# x-OSC_Gloves_v6.net
KiCad netlist of a schematic drawn in EAGLE
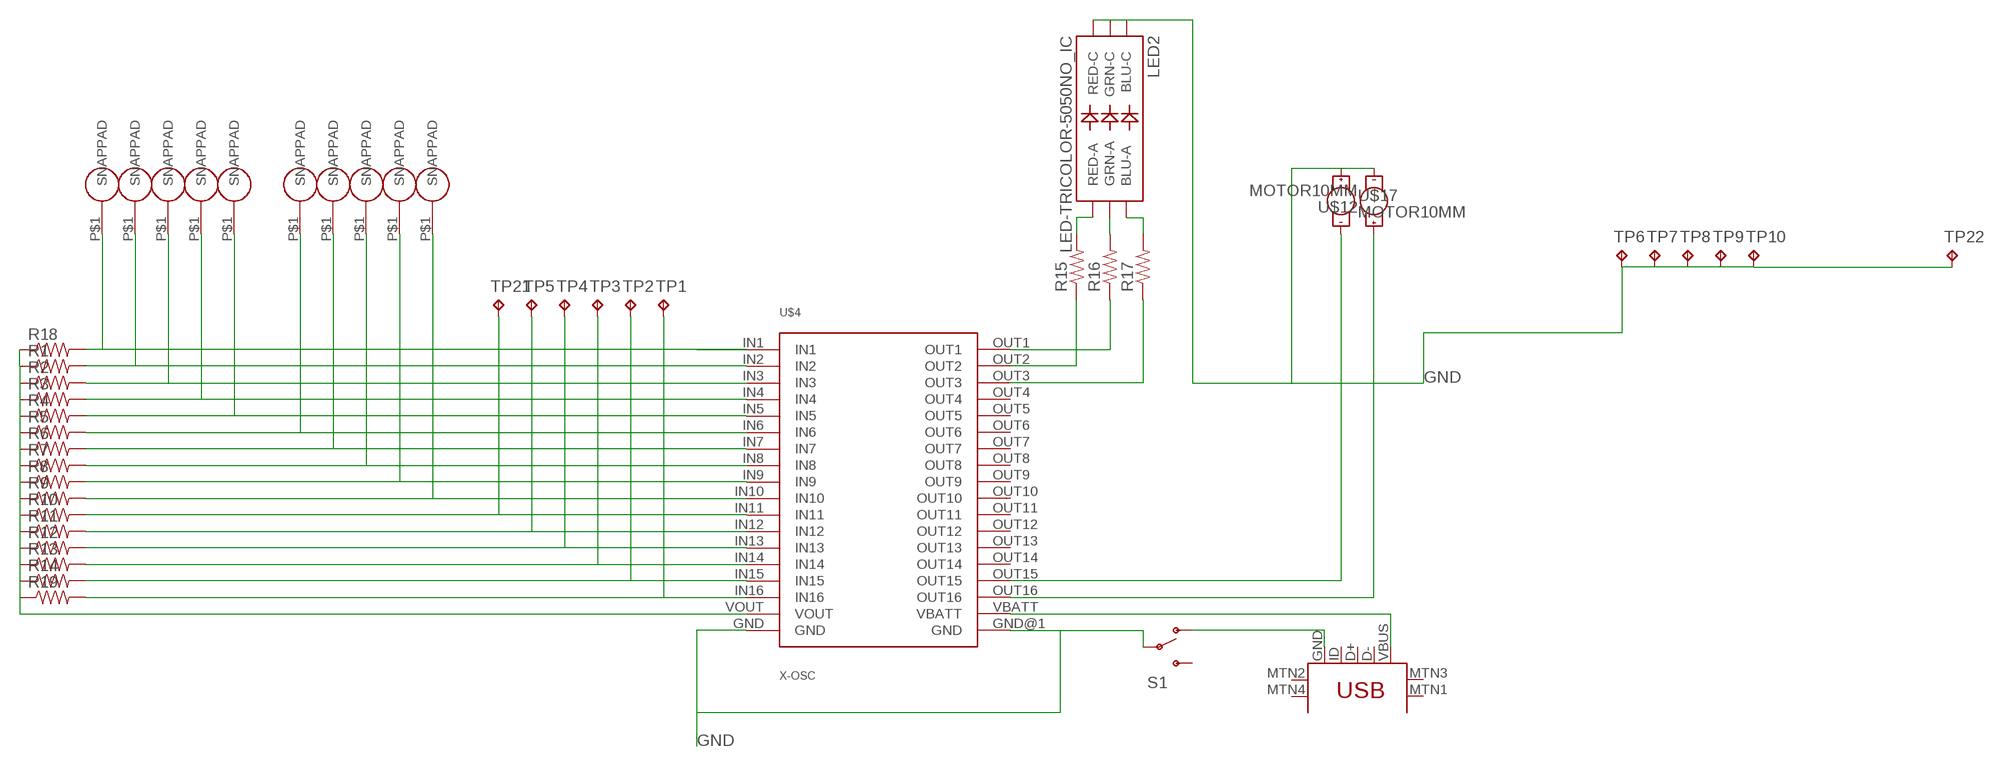
[diagram p0: schematic, sheet 1]

(export (version "E")
  (design (tool "Eeschema 10.0.6"))
  (components
    (comp (ref "LED2")
      (value "LED-TRICOLOR-5050NO_IC")
      (footprint "eagle-import:LED-TRICOLOR-5050")
      (libsource (lib "eagle-import") (part "LED-TRICOLOR-5050NO_IC"))
    )
    (comp (ref "R1")
      (value "RESISTOR0805-RES")
      (footprint "eagle-import:0805")
      (libsource (lib "eagle-import") (part "RESISTOR0805-RES"))
    )
    (comp (ref "R2")
      (value "RESISTOR0805-RES")
      (footprint "eagle-import:0805")
      (libsource (lib "eagle-import") (part "RESISTOR0805-RES"))
    )
    (comp (ref "R3")
      (value "RESISTOR0805-RES")
      (footprint "eagle-import:0805")
      (libsource (lib "eagle-import") (part "RESISTOR0805-RES"))
    )
    (comp (ref "R4")
      (value "RESISTOR0805-RES")
      (footprint "eagle-import:0805")
      (libsource (lib "eagle-import") (part "RESISTOR0805-RES"))
    )
    (comp (ref "R5")
      (value "RESISTOR0805-RES")
      (footprint "eagle-import:0805")
      (libsource (lib "eagle-import") (part "RESISTOR0805-RES"))
    )
    (comp (ref "R6")
      (value "RESISTOR0805-RES")
      (footprint "eagle-import:0805")
      (libsource (lib "eagle-import") (part "RESISTOR0805-RES"))
    )
    (comp (ref "R7")
      (value "RESISTOR0805-RES")
      (footprint "eagle-import:0805")
      (libsource (lib "eagle-import") (part "RESISTOR0805-RES"))
    )
    (comp (ref "R8")
      (value "RESISTOR0805-RES")
      (footprint "eagle-import:0805")
      (libsource (lib "eagle-import") (part "RESISTOR0805-RES"))
    )
    (comp (ref "R9")
      (value "RESISTOR0805-RES")
      (footprint "eagle-import:0805")
      (libsource (lib "eagle-import") (part "RESISTOR0805-RES"))
    )
    (comp (ref "R10")
      (value "RESISTOR0805-RES")
      (footprint "eagle-import:0805")
      (libsource (lib "eagle-import") (part "RESISTOR0805-RES"))
    )
    (comp (ref "R11")
      (value "RESISTOR0805-RES")
      (footprint "eagle-import:0805")
      (libsource (lib "eagle-import") (part "RESISTOR0805-RES"))
    )
    (comp (ref "R12")
      (value "RESISTOR0805-RES")
      (footprint "eagle-import:0805")
      (libsource (lib "eagle-import") (part "RESISTOR0805-RES"))
    )
    (comp (ref "R13")
      (value "RESISTOR0805-RES")
      (footprint "eagle-import:0805")
      (libsource (lib "eagle-import") (part "RESISTOR0805-RES"))
    )
    (comp (ref "R14")
      (value "RESISTOR0805-RES")
      (footprint "eagle-import:0805")
      (libsource (lib "eagle-import") (part "RESISTOR0805-RES"))
    )
    (comp (ref "R15")
      (value "RESISTOR0805-RES")
      (footprint "eagle-import:0805")
      (libsource (lib "eagle-import") (part "RESISTOR0805-RES"))
    )
    (comp (ref "R16")
      (value "RESISTOR0805-RES")
      (footprint "eagle-import:0805")
      (libsource (lib "eagle-import") (part "RESISTOR0805-RES"))
    )
    (comp (ref "R17")
      (value "RESISTOR0805-RES")
      (footprint "eagle-import:0805")
      (libsource (lib "eagle-import") (part "RESISTOR0805-RES"))
    )
    (comp (ref "R18")
      (value "RESISTOR0805-RES")
      (footprint "eagle-import:0805")
      (libsource (lib "eagle-import") (part "RESISTOR0805-RES"))
    )
    (comp (ref "R19")
      (value "RESISTOR0805-RES")
      (footprint "eagle-import:0805")
      (libsource (lib "eagle-import") (part "RESISTOR0805-RES"))
    )
    (comp (ref "S1")
      (value "SWITCH-SPDT-SMD-A")
      (footprint "eagle-import:SWITCH-SPST-SMD-A")
      (libsource (lib "eagle-import") (part "SWITCH-SPDT-SMD-A"))
    )
    (comp (ref "TP1")
      (value "TPTP20R")
      (footprint "eagle-import:TP20R")
      (libsource (lib "eagle-import") (part "TPTP20R"))
    )
    (comp (ref "TP2")
      (value "TPTP20R")
      (footprint "eagle-import:TP20R")
      (libsource (lib "eagle-import") (part "TPTP20R"))
    )
    (comp (ref "TP3")
      (value "TPTP20R")
      (footprint "eagle-import:TP20R")
      (libsource (lib "eagle-import") (part "TPTP20R"))
    )
    (comp (ref "TP4")
      (value "TPTP20R")
      (footprint "eagle-import:TP20R")
      (libsource (lib "eagle-import") (part "TPTP20R"))
    )
    (comp (ref "TP5")
      (value "TPTP20R")
      (footprint "eagle-import:TP20R")
      (libsource (lib "eagle-import") (part "TPTP20R"))
    )
    (comp (ref "TP6")
      (value "TPTP20R")
      (footprint "eagle-import:TP20R")
      (libsource (lib "eagle-import") (part "TPTP20R"))
    )
    (comp (ref "TP7")
      (value "TPTP20R")
      (footprint "eagle-import:TP20R")
      (libsource (lib "eagle-import") (part "TPTP20R"))
    )
    (comp (ref "TP8")
      (value "TPTP20R")
      (footprint "eagle-import:TP20R")
      (libsource (lib "eagle-import") (part "TPTP20R"))
    )
    (comp (ref "TP9")
      (value "TPTP20R")
      (footprint "eagle-import:TP20R")
      (libsource (lib "eagle-import") (part "TPTP20R"))
    )
    (comp (ref "TP10")
      (value "TPTP20R")
      (footprint "eagle-import:TP20R")
      (libsource (lib "eagle-import") (part "TPTP20R"))
    )
    (comp (ref "TP21")
      (value "TPTP20R")
      (footprint "eagle-import:TP20R")
      (libsource (lib "eagle-import") (part "TPTP20R"))
    )
    (comp (ref "TP22")
      (value "TPTP20R")
      (footprint "eagle-import:TP20R")
      (libsource (lib "eagle-import") (part "TPTP20R"))
    )
    (comp (ref "U$1")
      (value "SNAP-PAD_7MM_ROUND")
      (footprint "eagle-import:SNAP-PAD_7MM_RD")
      (libsource (lib "eagle-import") (part "SNAP-PAD_7MM_ROUND"))
    )
    (comp (ref "U$2")
      (value "SNAP-PAD_7MM_ROUND")
      (footprint "eagle-import:SNAP-PAD_7MM_RD")
      (libsource (lib "eagle-import") (part "SNAP-PAD_7MM_ROUND"))
    )
    (comp (ref "U$3")
      (value "SNAP-PAD_7MM_ROUND")
      (footprint "eagle-import:SNAP-PAD_7MM_RD")
      (libsource (lib "eagle-import") (part "SNAP-PAD_7MM_ROUND"))
    )
    (comp (ref "U$4")
      (value "X-OSC")
      (footprint "eagle-import:X-OSC_SMD")
      (libsource (lib "eagle-import") (part "X-OSC"))
    )
    (comp (ref "U$5")
      (value "USB-MINIB-5PIN")
      (footprint "eagle-import:USB-MINIB")
      (libsource (lib "eagle-import") (part "USB-MINIB-5PIN"))
    )
    (comp (ref "U$6")
      (value "SNAP-PAD_7MM_ROUND")
      (footprint "eagle-import:SNAP-PAD_7MM_RD")
      (libsource (lib "eagle-import") (part "SNAP-PAD_7MM_ROUND"))
    )
    (comp (ref "U$7")
      (value "SNAP-PAD_7MM_ROUND")
      (footprint "eagle-import:SNAP-PAD_7MM_RD")
      (libsource (lib "eagle-import") (part "SNAP-PAD_7MM_ROUND"))
    )
    (comp (ref "U$8")
      (value "SNAP-PAD_7MM_ROUND")
      (footprint "eagle-import:SNAP-PAD_7MM_RD")
      (libsource (lib "eagle-import") (part "SNAP-PAD_7MM_ROUND"))
    )
    (comp (ref "U$9")
      (value "SNAP-PAD_7MM_ROUND")
      (footprint "eagle-import:SNAP-PAD_7MM_RD")
      (libsource (lib "eagle-import") (part "SNAP-PAD_7MM_ROUND"))
    )
    (comp (ref "U$10")
      (value "SNAP-PAD_7MM_ROUND")
      (footprint "eagle-import:SNAP-PAD_7MM_RD")
      (libsource (lib "eagle-import") (part "SNAP-PAD_7MM_ROUND"))
    )
    (comp (ref "U$11")
      (value "SNAP-PAD_7MM_ROUND")
      (footprint "eagle-import:SNAP-PAD_7MM_RD")
      (libsource (lib "eagle-import") (part "SNAP-PAD_7MM_ROUND"))
    )
    (comp (ref "U$12")
      (value "MOTOR10MM")
      (footprint "eagle-import:VIBE-MOTOR-10MM")
      (libsource (lib "eagle-import") (part "MOTOR10MM"))
    )
    (comp (ref "U$17")
      (value "MOTOR10MM")
      (footprint "eagle-import:VIBE-MOTOR-10MM")
      (libsource (lib "eagle-import") (part "MOTOR10MM"))
    )
    (comp (ref "U$21")
      (value "SNAP-PAD_7MM_ROUND")
      (footprint "eagle-import:SNAP-PAD_7MM_RD")
      (libsource (lib "eagle-import") (part "SNAP-PAD_7MM_ROUND"))
    )
  )
  (nets
    (net (code "1") (name "/GND") (class "Default")
      (node (ref "LED2") (pin "4") (pinfunction "BLU-C_4") (pintype "bidirectional"))
      (node (ref "LED2") (pin "5") (pinfunction "RED-C_5") (pintype "bidirectional"))
      (node (ref "LED2") (pin "6") (pinfunction "GRN-C_6") (pintype "bidirectional"))
      (node (ref "S1") (pin "2") (pinfunction "P_2") (pintype "passive"))
      (node (ref "TP10") (pin "TP") (pinfunction "TP_TP") (pintype "input"))
      (node (ref "TP22") (pin "TP") (pinfunction "TP_TP") (pintype "input"))
      (node (ref "TP6") (pin "TP") (pinfunction "TP_TP") (pintype "input"))
      (node (ref "TP7") (pin "TP") (pinfunction "TP_TP") (pintype "input"))
      (node (ref "TP8") (pin "TP") (pinfunction "TP_TP") (pintype "input"))
      (node (ref "TP9") (pin "TP") (pinfunction "TP_TP") (pintype "input"))
      (node (ref "U$12") (pin "-") (pinfunction "-_-") (pintype "bidirectional"))
      (node (ref "U$17") (pin "+") (pinfunction "+_+") (pintype "bidirectional"))
      (node (ref "U$4") (pin "GND") (pinfunction "GND_GND") (pintype "bidirectional"))
      (node (ref "U$4") (pin "GND@1") (pinfunction "GND_GND@1") (pintype "bidirectional"))
    )
    (net (code "2") (name "Net-(LED2-BLU-A)") (class "Default")
      (node (ref "LED2") (pin "3") (pinfunction "BLU-A_3") (pintype "bidirectional"))
      (node (ref "R17") (pin "2") (pinfunction "2_2") (pintype "passive"))
    )
    (net (code "3") (name "Net-(LED2-GRN-A)") (class "Default")
      (node (ref "LED2") (pin "1") (pinfunction "GRN-A_1") (pintype "bidirectional"))
      (node (ref "R16") (pin "2") (pinfunction "2_2") (pintype "passive"))
    )
    (net (code "4") (name "Net-(LED2-RED-A)") (class "Default")
      (node (ref "LED2") (pin "2") (pinfunction "RED-A_2") (pintype "bidirectional"))
      (node (ref "R15") (pin "2") (pinfunction "2_2") (pintype "passive"))
    )
    (net (code "5") (name "Net-(R1-Pad1)") (class "Default")
      (node (ref "R1") (pin "1") (pinfunction "1_1") (pintype "passive"))
      (node (ref "R10") (pin "1") (pinfunction "1_1") (pintype "passive"))
      (node (ref "R11") (pin "1") (pinfunction "1_1") (pintype "passive"))
      (node (ref "R12") (pin "1") (pinfunction "1_1") (pintype "passive"))
      (node (ref "R13") (pin "1") (pinfunction "1_1") (pintype "passive"))
      (node (ref "R14") (pin "1") (pinfunction "1_1") (pintype "passive"))
      (node (ref "R18") (pin "1") (pinfunction "1_1") (pintype "passive"))
      (node (ref "R19") (pin "1") (pinfunction "1_1") (pintype "passive"))
      (node (ref "R2") (pin "1") (pinfunction "1_1") (pintype "passive"))
      (node (ref "R3") (pin "1") (pinfunction "1_1") (pintype "passive"))
      (node (ref "R4") (pin "1") (pinfunction "1_1") (pintype "passive"))
      (node (ref "R5") (pin "1") (pinfunction "1_1") (pintype "passive"))
      (node (ref "R6") (pin "1") (pinfunction "1_1") (pintype "passive"))
      (node (ref "R7") (pin "1") (pinfunction "1_1") (pintype "passive"))
      (node (ref "R8") (pin "1") (pinfunction "1_1") (pintype "passive"))
      (node (ref "R9") (pin "1") (pinfunction "1_1") (pintype "passive"))
      (node (ref "U$4") (pin "VOUT") (pinfunction "VOUT_VOUT") (pintype "bidirectional"))
    )
    (net (code "6") (name "Net-(R10-Pad2)") (class "Default")
      (node (ref "R10") (pin "2") (pinfunction "2_2") (pintype "passive"))
      (node (ref "TP21") (pin "TP") (pinfunction "TP_TP") (pintype "input"))
      (node (ref "U$4") (pin "IN11") (pinfunction "IN11_IN11") (pintype "bidirectional"))
    )
    (net (code "7") (name "Net-(R11-Pad2)") (class "Default")
      (node (ref "R11") (pin "2") (pinfunction "2_2") (pintype "passive"))
      (node (ref "TP5") (pin "TP") (pinfunction "TP_TP") (pintype "input"))
      (node (ref "U$4") (pin "IN12") (pinfunction "IN12_IN12") (pintype "bidirectional"))
    )
    (net (code "8") (name "Net-(R12-Pad2)") (class "Default")
      (node (ref "R12") (pin "2") (pinfunction "2_2") (pintype "passive"))
      (node (ref "TP4") (pin "TP") (pinfunction "TP_TP") (pintype "input"))
      (node (ref "U$4") (pin "IN13") (pinfunction "IN13_IN13") (pintype "bidirectional"))
    )
    (net (code "9") (name "Net-(R13-Pad2)") (class "Default")
      (node (ref "R13") (pin "2") (pinfunction "2_2") (pintype "passive"))
      (node (ref "TP3") (pin "TP") (pinfunction "TP_TP") (pintype "input"))
      (node (ref "U$4") (pin "IN14") (pinfunction "IN14_IN14") (pintype "bidirectional"))
    )
    (net (code "10") (name "Net-(R14-Pad2)") (class "Default")
      (node (ref "R14") (pin "2") (pinfunction "2_2") (pintype "passive"))
      (node (ref "TP2") (pin "TP") (pinfunction "TP_TP") (pintype "input"))
      (node (ref "U$4") (pin "IN15") (pinfunction "IN15_IN15") (pintype "bidirectional"))
    )
    (net (code "11") (name "Net-(R15-Pad1)") (class "Default")
      (node (ref "R15") (pin "1") (pinfunction "1_1") (pintype "passive"))
      (node (ref "U$4") (pin "OUT2") (pinfunction "OUT2_OUT2") (pintype "bidirectional"))
    )
    (net (code "12") (name "Net-(R16-Pad1)") (class "Default")
      (node (ref "R16") (pin "1") (pinfunction "1_1") (pintype "passive"))
      (node (ref "U$4") (pin "OUT1") (pinfunction "OUT1_OUT1") (pintype "bidirectional"))
    )
    (net (code "13") (name "Net-(R17-Pad1)") (class "Default")
      (node (ref "R17") (pin "1") (pinfunction "1_1") (pintype "passive"))
      (node (ref "U$4") (pin "OUT3") (pinfunction "OUT3_OUT3") (pintype "bidirectional"))
    )
    (net (code "14") (name "Net-(R19-Pad2)") (class "Default")
      (node (ref "R19") (pin "2") (pinfunction "2_2") (pintype "passive"))
      (node (ref "TP1") (pin "TP") (pinfunction "TP_TP") (pintype "input"))
      (node (ref "U$4") (pin "IN16") (pinfunction "IN16_IN16") (pintype "bidirectional"))
    )
    (net (code "15") (name "Net-(S1-O)") (class "Default")
      (node (ref "S1") (pin "1") (pinfunction "O_1") (pintype "passive"))
      (node (ref "U$5") (pin "GND") (pinfunction "GND_GND") (pintype "bidirectional"))
    )
    (net (code "16") (name "Net-(U$1-SNAPPAD)") (class "Default")
      (node (ref "R1") (pin "2") (pinfunction "2_2") (pintype "passive"))
      (node (ref "U$1") (pin "P$1") (pinfunction "SNAPPAD_P$1") (pintype "bidirectional"))
      (node (ref "U$4") (pin "IN2") (pinfunction "IN2_IN2") (pintype "bidirectional"))
    )
    (net (code "17") (name "Net-(U$2-SNAPPAD)") (class "Default")
      (node (ref "R2") (pin "2") (pinfunction "2_2") (pintype "passive"))
      (node (ref "U$2") (pin "P$1") (pinfunction "SNAPPAD_P$1") (pintype "bidirectional"))
      (node (ref "U$4") (pin "IN3") (pinfunction "IN3_IN3") (pintype "bidirectional"))
    )
    (net (code "18") (name "Net-(U$3-SNAPPAD)") (class "Default")
      (node (ref "R3") (pin "2") (pinfunction "2_2") (pintype "passive"))
      (node (ref "U$3") (pin "P$1") (pinfunction "SNAPPAD_P$1") (pintype "bidirectional"))
      (node (ref "U$4") (pin "IN4") (pinfunction "IN4_IN4") (pintype "bidirectional"))
    )
    (net (code "19") (name "Net-(U$4-PadVBATT)") (class "Default")
      (node (ref "U$4") (pin "VBATT") (pinfunction "VBATT_VBATT") (pintype "bidirectional"))
      (node (ref "U$5") (pin "VBUS") (pinfunction "VBUS_VBUS") (pintype "bidirectional"))
    )
    (net (code "20") (name "Net-(U$6-SNAPPAD)") (class "Default")
      (node (ref "R4") (pin "2") (pinfunction "2_2") (pintype "passive"))
      (node (ref "U$4") (pin "IN5") (pinfunction "IN5_IN5") (pintype "bidirectional"))
      (node (ref "U$6") (pin "P$1") (pinfunction "SNAPPAD_P$1") (pintype "bidirectional"))
    )
    (net (code "21") (name "Net-(U$7-SNAPPAD)") (class "Default")
      (node (ref "R5") (pin "2") (pinfunction "2_2") (pintype "passive"))
      (node (ref "U$4") (pin "IN6") (pinfunction "IN6_IN6") (pintype "bidirectional"))
      (node (ref "U$7") (pin "P$1") (pinfunction "SNAPPAD_P$1") (pintype "bidirectional"))
    )
    (net (code "22") (name "Net-(U$8-SNAPPAD)") (class "Default")
      (node (ref "R6") (pin "2") (pinfunction "2_2") (pintype "passive"))
      (node (ref "U$4") (pin "IN7") (pinfunction "IN7_IN7") (pintype "bidirectional"))
      (node (ref "U$8") (pin "P$1") (pinfunction "SNAPPAD_P$1") (pintype "bidirectional"))
    )
    (net (code "23") (name "Net-(U$9-SNAPPAD)") (class "Default")
      (node (ref "R7") (pin "2") (pinfunction "2_2") (pintype "passive"))
      (node (ref "U$4") (pin "IN8") (pinfunction "IN8_IN8") (pintype "bidirectional"))
      (node (ref "U$9") (pin "P$1") (pinfunction "SNAPPAD_P$1") (pintype "bidirectional"))
    )
    (net (code "24") (name "Net-(U$10-SNAPPAD)") (class "Default")
      (node (ref "R8") (pin "2") (pinfunction "2_2") (pintype "passive"))
      (node (ref "U$10") (pin "P$1") (pinfunction "SNAPPAD_P$1") (pintype "bidirectional"))
      (node (ref "U$4") (pin "IN9") (pinfunction "IN9_IN9") (pintype "bidirectional"))
    )
    (net (code "25") (name "Net-(U$11-SNAPPAD)") (class "Default")
      (node (ref "R9") (pin "2") (pinfunction "2_2") (pintype "passive"))
      (node (ref "U$11") (pin "P$1") (pinfunction "SNAPPAD_P$1") (pintype "bidirectional"))
      (node (ref "U$4") (pin "IN10") (pinfunction "IN10_IN10") (pintype "bidirectional"))
    )
    (net (code "26") (name "Net-(U$12-Pad+)") (class "Default")
      (node (ref "U$12") (pin "+") (pinfunction "+_+") (pintype "bidirectional"))
      (node (ref "U$4") (pin "OUT16") (pinfunction "OUT16_OUT16") (pintype "bidirectional"))
    )
    (net (code "27") (name "Net-(U$17-Pad-)") (class "Default")
      (node (ref "U$17") (pin "-") (pinfunction "-_-") (pintype "bidirectional"))
      (node (ref "U$4") (pin "OUT15") (pinfunction "OUT15_OUT15") (pintype "bidirectional"))
    )
    (net (code "28") (name "Net-(U$21-SNAPPAD)") (class "Default")
      (node (ref "R18") (pin "2") (pinfunction "2_2") (pintype "passive"))
      (node (ref "U$21") (pin "P$1") (pinfunction "SNAPPAD_P$1") (pintype "bidirectional"))
      (node (ref "U$4") (pin "IN1") (pinfunction "IN1_IN1") (pintype "bidirectional"))
    )
    (net (code "29") (name "unconnected-(S1-S-Pad3)") (class "Default")
      (node (ref "S1") (pin "3") (pinfunction "S_3") (pintype "passive"))
    )
    (net (code "30") (name "unconnected-(U$4-PadOUT4)") (class "Default")
      (node (ref "U$4") (pin "OUT4") (pinfunction "OUT4_OUT4") (pintype "bidirectional"))
    )
    (net (code "31") (name "unconnected-(U$4-PadOUT5)") (class "Default")
      (node (ref "U$4") (pin "OUT5") (pinfunction "OUT5_OUT5") (pintype "bidirectional"))
    )
    (net (code "32") (name "unconnected-(U$4-PadOUT6)") (class "Default")
      (node (ref "U$4") (pin "OUT6") (pinfunction "OUT6_OUT6") (pintype "bidirectional"))
    )
    (net (code "33") (name "unconnected-(U$4-PadOUT7)") (class "Default")
      (node (ref "U$4") (pin "OUT7") (pinfunction "OUT7_OUT7") (pintype "bidirectional"))
    )
    (net (code "34") (name "unconnected-(U$4-PadOUT8)") (class "Default")
      (node (ref "U$4") (pin "OUT8") (pinfunction "OUT8_OUT8") (pintype "bidirectional"))
    )
    (net (code "35") (name "unconnected-(U$4-PadOUT9)") (class "Default")
      (node (ref "U$4") (pin "OUT9") (pinfunction "OUT9_OUT9") (pintype "bidirectional"))
    )
    (net (code "36") (name "unconnected-(U$4-PadOUT10)") (class "Default")
      (node (ref "U$4") (pin "OUT10") (pinfunction "OUT10_OUT10") (pintype "bidirectional"))
    )
    (net (code "37") (name "unconnected-(U$4-PadOUT11)") (class "Default")
      (node (ref "U$4") (pin "OUT11") (pinfunction "OUT11_OUT11") (pintype "bidirectional"))
    )
    (net (code "38") (name "unconnected-(U$4-PadOUT12)") (class "Default")
      (node (ref "U$4") (pin "OUT12") (pinfunction "OUT12_OUT12") (pintype "bidirectional"))
    )
    (net (code "39") (name "unconnected-(U$4-PadOUT13)") (class "Default")
      (node (ref "U$4") (pin "OUT13") (pinfunction "OUT13_OUT13") (pintype "bidirectional"))
    )
    (net (code "40") (name "unconnected-(U$4-PadOUT14)") (class "Default")
      (node (ref "U$4") (pin "OUT14") (pinfunction "OUT14_OUT14") (pintype "bidirectional"))
    )
    (net (code "41") (name "unconnected-(U$5-MTN1-PadMTN3)") (class "Default")
      (node (ref "U$5") (pin "MTN3") (pinfunction "MTN1_MTN3") (pintype "bidirectional"))
    )
    (net (code "42") (name "unconnected-(U$5-MTN2-PadMTN1)") (class "Default")
      (node (ref "U$5") (pin "MTN1") (pinfunction "MTN2_MTN1") (pintype "bidirectional"))
    )
    (net (code "43") (name "unconnected-(U$5-MTN3-PadMTN2)") (class "Default")
      (node (ref "U$5") (pin "MTN2") (pinfunction "MTN3_MTN2") (pintype "bidirectional"))
    )
    (net (code "44") (name "unconnected-(U$5-PadD+)") (class "Default")
      (node (ref "U$5") (pin "D+") (pinfunction "D+_D+") (pintype "bidirectional"))
    )
    (net (code "45") (name "unconnected-(U$5-PadD-)") (class "Default")
      (node (ref "U$5") (pin "D-") (pinfunction "D-_D-") (pintype "bidirectional"))
    )
    (net (code "46") (name "unconnected-(U$5-PadID)") (class "Default")
      (node (ref "U$5") (pin "ID") (pinfunction "ID_ID") (pintype "bidirectional"))
    )
    (net (code "47") (name "unconnected-(U$5-PadMTN4)") (class "Default")
      (node (ref "U$5") (pin "MTN4") (pinfunction "MTN4_MTN4") (pintype "bidirectional"))
    )
  )
)
